# 230C_12V_PSU_TPS40200.net
KiCad netlist of a schematic drawn in Altium Designer
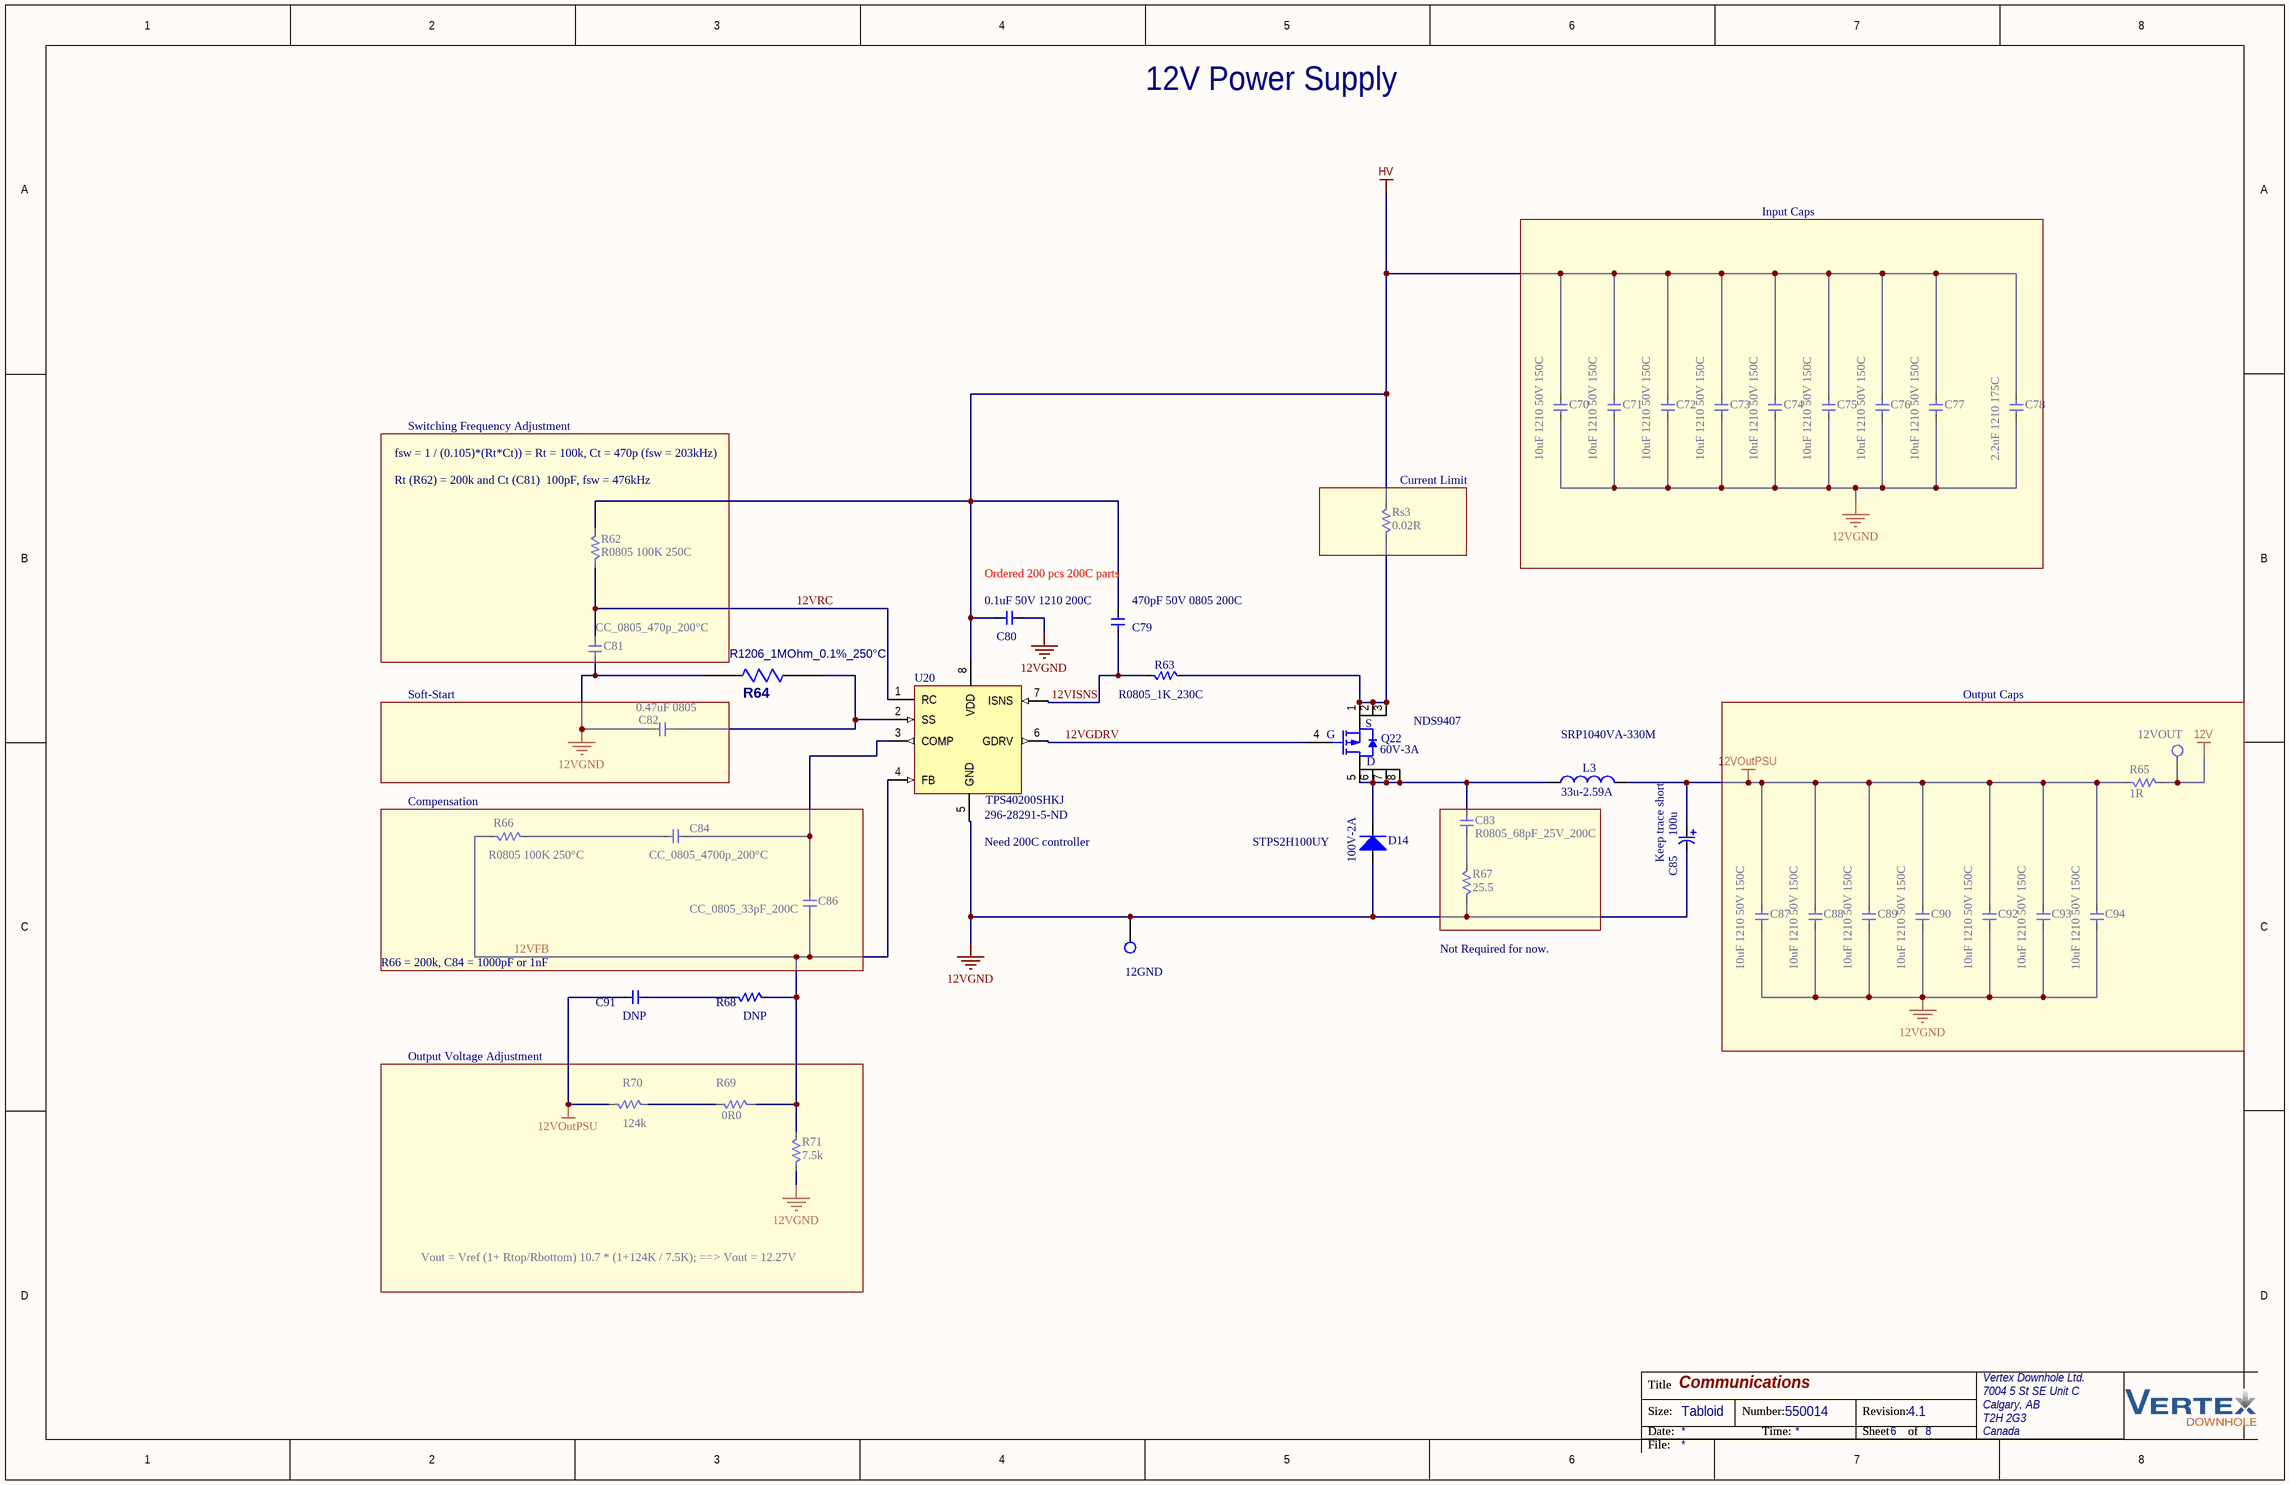
[diagram p0: 230C_12V_PSU_TPS40200.SchDoc]

(export (version "E")
  (design (tool "Eeschema 10.0.6"))
  (components
    (comp (ref "5")
      (value "12VOUT")
      (footprint "TP-S")
      (description "Test  Point")
      (libsource (lib "Miscellaneous") (part "TP"))
    )
    (comp (ref "6")
      (value "12GND")
      (footprint "TP-S")
      (description "Test  Point")
      (libsource (lib "Miscellaneous") (part "TP"))
    )
    (comp (ref "C70")
      (value "10uF 1210 50V 150C")
      (footprint "1210")
      (description "CAP CER 0.1UF 50V C0G/NP0 1210 200C")
      (fields (field (name "VOLTAGE") "50V") (field (name "TOLERANCE") "±10%"))
      (libsource (lib "230C_PSU_TPS40200") (part "CC-1210"))
    )
    (comp (ref "C71")
      (value "10uF 1210 50V 150C")
      (footprint "1210")
      (description "CAP CER 0.1UF 50V C0G/NP0 1210 200C")
      (fields (field (name "VOLTAGE") "50V") (field (name "TOLERANCE") "±5%"))
      (libsource (lib "230C_PSU_TPS40200") (part "CC-1210"))
    )
    (comp (ref "C72")
      (value "10uF 1210 50V 150C")
      (footprint "1210")
      (description "CAP CER 0.1UF 50V C0G/NP0 1210 200C")
      (fields (field (name "VOLTAGE") "50V") (field (name "TOLERANCE") "±5%"))
      (libsource (lib "230C_PSU_TPS40200") (part "CC-1210"))
    )
    (comp (ref "C73")
      (value "10uF 1210 50V 150C")
      (footprint "1210")
      (description "CAP CER 0.1UF 50V C0G/NP0 1210 200C")
      (fields (field (name "VOLTAGE") "50V") (field (name "TOLERANCE") "±5%"))
      (libsource (lib "230C_PSU_TPS40200") (part "CC-1210"))
    )
    (comp (ref "C74")
      (value "10uF 1210 50V 150C")
      (footprint "1210")
      (description "CAP CER 0.1UF 50V C0G/NP0 1210 200C")
      (fields (field (name "VOLTAGE") "50V") (field (name "TOLERANCE") "±5%"))
      (libsource (lib "230C_PSU_TPS40200") (part "CC-1210"))
    )
    (comp (ref "C75")
      (value "10uF 1210 50V 150C")
      (footprint "1210")
      (description "CAP CER 0.1UF 50V C0G/NP0 1210 200C")
      (fields (field (name "VOLTAGE") "50V") (field (name "TOLERANCE") "±5%"))
      (libsource (lib "230C_PSU_TPS40200") (part "CC-1210"))
    )
    (comp (ref "C76")
      (value "10uF 1210 50V 150C")
      (footprint "1210")
      (description "CAP CER 0.1UF 50V C0G/NP0 1210 200C")
      (fields (field (name "VOLTAGE") "50V") (field (name "TOLERANCE") "±5%"))
      (libsource (lib "230C_PSU_TPS40200") (part "CC-1210"))
    )
    (comp (ref "C77")
      (value "10uF 1210 50V 150C")
      (footprint "1210")
      (description "CAP CER 0.1UF 50V C0G/NP0 1210 200C")
      (fields (field (name "VOLTAGE") "50V") (field (name "TOLERANCE") "±5%"))
      (libsource (lib "230C_PSU_TPS40200") (part "CC-1210"))
    )
    (comp (ref "C78")
      (value "2.2uF 1210 175C")
      (footprint "1210")
      (description "CAP CER 0.1UF 50V C0G/NP0 1210 200C")
      (fields (field (name "VOLTAGE") "25V") (field (name "TOLERANCE") "±5%"))
      (libsource (lib "230C_PSU_TPS40200") (part "CC-1210"))
    )
    (comp (ref "C79")
      (value "470pF 50V 0805 200C")
      (footprint "1210")
      (description "CAP CER 470PF 50V C0G/NP0 0805 200C")
      (fields (field (name "VOLTAGE") "100V") (field (name "TOLERANCE") "±5%"))
      (libsource (lib "Schlib_CES2018") (part "CC-0805-100p-100V-10%-200C-NP0"))
    )
    (comp (ref "C80")
      (value "0.1uF 50V 1210 200C")
      (footprint "0805")
      (description "CAP CER 0.1UF 50V C0G/NP0 1210 200C")
      (fields (field (name "VOLTAGE") "25V") (field (name "TOLERANCE") "±5%"))
      (libsource (lib "230C_PSU_TPS40200") (part "CC-1210"))
    )
    (comp (ref "C81")
      (value "CC_0805_470p_200°C")
      (footprint "0805")
      (description "CAPACITOR CER 470PF 100V C0G/NP0 0805")
      (fields (field (name "VOLTAGE") "100V") (field (name "TOLERANCE") "±10%"))
      (libsource (lib "Integrated_Library_CES2018") (part "CC-0805-470p-100V-10%-150C-NP0"))
    )
    (comp (ref "C82")
      (value "0.47uF 0805")
      (footprint "0805")
      (description "CAPACITOR CER 0.047UF 25V C0G/NP0 0805")
      (fields (field (name "VOLTAGE") "25V") (field (name "TOLERANCE") "±5%"))
      (libsource (lib "Integrated_Library_CES2018") (part "CC-0805-47n-25V-5%-125C-NP0"))
    )
    (comp (ref "C83")
      (value "R0805_68pF_25V_200C")
      (footprint "0805")
      (description "CAPACITOR CER 2200PF 100V C0G/NP0 0805")
      (fields (field (name "VOLTAGE") "100V") (field (name "TOLERANCE") "±5%"))
      (libsource (lib "Schlib_CES2018") (part "CC-0805-2200p-100V-5%-200C-NP0"))
    )
    (comp (ref "C84")
      (value "CC_0805_4700p_200°C")
      (footprint "0805")
      (description "CAPACITOR CER 2200PF 100V C0G/NP0 0805")
      (fields (field (name "VOLTAGE") "100V") (field (name "TOLERANCE") "±5%"))
      (libsource (lib "Schlib_CES2018") (part "CC-0805-2200p-100V-5%-200C-NP0"))
    )
    (comp (ref "C85")
      (value "100u")
      (footprint "0805")
      (description "CAPACITOR TANT 100UF 16V 10% 2917")
      (fields (field (name "VOLTAGE") "16V") (field (name "TOLERANCE") "±10%"))
      (libsource (lib "Integrated_Library_CES2018") (part "CT-2917-100u-16V-10%-150C"))
    )
    (comp (ref "C86")
      (value "CC_0805_33pF_200C")
      (footprint "1210")
      (description "CAPACITOR CER 120PF 250V NP0 0805")
      (fields (field (name "VOLTAGE") "250V") (field (name "TOLERANCE") "±5%"))
      (libsource (lib "Schlib_CES2018") (part "CC-0805-120p-100V-5%-200C-NP0"))
    )
    (comp (ref "C87")
      (value "10uF 1210 50V 150C")
      (footprint "1210")
      (description "CAP CER 0.1UF 50V C0G/NP0 1210 200C")
      (fields (field (name "VOLTAGE") "50V") (field (name "TOLERANCE") "±10%"))
      (libsource (lib "230C_PSU_TPS40200") (part "CC-1210"))
    )
    (comp (ref "C88")
      (value "10uF 1210 50V 150C")
      (footprint "1210")
      (description "CAP CER 0.1UF 50V C0G/NP0 1210 200C")
      (fields (field (name "VOLTAGE") "50V") (field (name "TOLERANCE") "±5%"))
      (libsource (lib "230C_PSU_TPS40200") (part "CC-1210"))
    )
    (comp (ref "C89")
      (value "10uF 1210 50V 150C")
      (footprint "1210")
      (description "CAP CER 0.1UF 50V C0G/NP0 1210 200C")
      (fields (field (name "VOLTAGE") "50V") (field (name "TOLERANCE") "±5%"))
      (libsource (lib "230C_PSU_TPS40200") (part "CC-1210"))
    )
    (comp (ref "C90")
      (value "10uF 1210 50V 150C")
      (footprint "1210")
      (description "CAP CER 0.1UF 50V C0G/NP0 1210 200C")
      (fields (field (name "VOLTAGE") "50V") (field (name "TOLERANCE") "±5%"))
      (libsource (lib "230C_PSU_TPS40200") (part "CC-1210"))
    )
    (comp (ref "C91")
      (value "C1206H104J3GACTU")
      (footprint "0603")
      (description "CAPACITOR CER 2700PF 50V X8R 0805")
      (libsource (lib "Integrated_Library_Greg") (part "CC-0805-2700p-50V-10%-150C"))
    )
    (comp (ref "C92")
      (value "10uF 1210 50V 150C")
      (footprint "1210")
      (description "CAP CER 0.1UF 50V C0G/NP0 1210 200C")
      (fields (field (name "VOLTAGE") "50V") (field (name "TOLERANCE") "±5%"))
      (libsource (lib "230C_PSU_TPS40200") (part "CC-1210"))
    )
    (comp (ref "C93")
      (value "10uF 1210 50V 150C")
      (footprint "1210")
      (description "CAP CER 0.1UF 50V C0G/NP0 1210 200C")
      (fields (field (name "VOLTAGE") "50V") (field (name "TOLERANCE") "±5%"))
      (libsource (lib "230C_PSU_TPS40200") (part "CC-1210"))
    )
    (comp (ref "C94")
      (value "10uF 1210 50V 150C")
      (footprint "1210")
      (description "CAP CER 0.1UF 50V C0G/NP0 1210 200C")
      (fields (field (name "VOLTAGE") "50V") (field (name "TOLERANCE") "±5%"))
      (libsource (lib "230C_PSU_TPS40200") (part "CC-1210"))
    )
    (comp (ref "D14")
      (value "100V-2A")
      (footprint "SMB")
      (description "DIODE SCHOTTKY 100V 2A SMB")
      (fields (field (name "VOLTAGE") "100V") (field (name "MFG") "STMicroelectronics"))
      (libsource (lib "Integrated_Library_CES2018") (part "DS-SMB-100V-2A"))
    )
    (comp (ref "L3")
      (value "33u-2.59A")
      (footprint "IND_CB_DRA125")
      (description "INDUCTOR 47UH 2.59A 81 MOHM")
      (fields (field (name "MFG") "Eaton") (field (name "TOLERANCE") "±20%"))
      (libsource (lib "Integrated_Library_CES2018") (part "LL-12.5X12.5-47u-2.59A"))
    )
    (comp (ref "Q22")
      (value "60V-3A")
      (footprint "SOIC_S9407_ONS")
      (description "MOSFET P-CH 60V 3A 8-SOIC")
      (fields (field (name "VOLTAGE") "60V") (field (name "MFG") "ON Semiconductor"))
      (libsource (lib "Integrated_Library_CES2018") (part "QF-SOIC8-PCH-60V-3A"))
    )
    (comp (ref "R62")
      (value "R0805 100K 250C")
      (footprint "0805")
      (description "100 kOhms ±0.1% 0.2W, 1/5W Chip Resistor 0805 (2012 Metric)")
      (fields (field (name "TOLERANCE") "±0.1%") (field (name "MFG") "Vishay Dale Thin Film"))
      (libsource (lib "Schlib_CES2018") (part "RS-0805-9.1K-0.1%-1/4W-155C"))
    )
    (comp (ref "R63")
      (value "R0805_1K_230C")
      (footprint "0805")
      (description "RESISTOR SMD 1K OHM 0.1% 1/8W 0805")
      (fields (field (name "TOLERANCE") "±1%") (field (name "MFG") "Vishay / Sfernice"))
      (libsource (lib "Schlib_CES2018") (part "RS-0805-1K-0.1%-1/8W-155C"))
    )
    (comp (ref "R64")
      (value "R1206_1MOhm_0.1%_250°C")
      (footprint "1206")
      (description "1206")
      (fields (field (name "MPN") "PATT1206E1004BGT1") (field (name "MFR") "Vishay Dale Thin Film"))
      (libsource (lib "BJPPS") (part "RC_1206"))
    )
    (comp (ref "R65")
      (value "1R")
      (footprint "0805")
      (description "RESISTOR SMD 1 OHM 1% 1/4W 0805")
      (fields (field (name "TOLERANCE") "±1%") (field (name "MFG") "Stackpole Electronics Inc."))
      (libsource (lib "Integrated_Library_Greg") (part "RS-0805-1R-1%-0.25W-155C"))
    )
    (comp (ref "R66")
      (value "R0805 100K 250°C")
      (footprint "0805")
      (description "100 kOhms ±0.1% 0.2W, 1/5W Chip Resistor 0805 (2012 Metric)")
      (fields (field (name "TOLERANCE") "±0.1%") (field (name "MFG") "Vishay Dale Thin Film"))
      (libsource (lib "Schlib_CES2018") (part "RS-0805-9.1K-0.1%-1/4W-155C"))
    )
    (comp (ref "R67")
      (value "25.5")
      (footprint "0805")
      (description "RESISTOR SMD 10.2K OHM 1% 1/4W 0805")
      (fields (field (name "TOLERANCE") "±1%") (field (name "MFG") "Panasonic Electronic Components"))
      (libsource (lib "Schlib_CES2018") (part "RS-0805-10.2K-0.1%-0.25W-155C"))
    )
    (comp (ref "R68")
      (value "ERJ-PB6B6812V")
      (footprint "0805")
      (description "RESISTOR SMD 475 OHM 0.1% 1/10W 0805")
      (libsource (lib "Schlib_CES2018") (part "RS-0805-475R-0.1%-0.25W-155C"))
    )
    (comp (ref "R69")
      (value "0R0")
      (footprint "0805")
      (fields
        (field (name "TOLERANCE") "±0.1%")
        (field (name "MFG") "Vishay Dale Thin Film")
        (field (name "POWER") "0.250W")
      )
      (libsource (lib "Schlib_CES2018") (part "RS-0805-1.5K-0.1%-1/4W-155C"))
    )
    (comp (ref "R70")
      (value "124k")
      (footprint "0805")
      (description "100 kOhms ±0.1% 0.2W, 1/5W Chip Resistor 0805 (2012 Metric)")
      (fields (field (name "TOLERANCE") "±0.1%") (field (name "MFG") "Vishay Dale Thin Film"))
      (libsource (lib "Schlib_CES2018") (part "RS-0805-9.1K-0.1%-1/4W-155C"))
    )
    (comp (ref "R71")
      (value "7.5k")
      (footprint "0805")
      (description "RESISTOR SMD 49.9 OHM 0.1% 1/25W 0805")
      (fields (field (name "TOLERANCE") "±0.1%") (field (name "MFG") "KOA Speer Electronics, Inc."))
      (libsource (lib "Schlib_CES2018") (part "RS-0805-49.9R-0.25%-0.25W-155C"))
    )
    (comp (ref "Rs3")
      (value "0.02R")
      (footprint "1206")
      (description "RESISTOR SMD 0.02 OHM 1% 1W 1206")
      (fields (field (name "TOLERANCE") "±1%") (field (name "MFG") "Panasonic Electronic Components"))
      (libsource (lib "Integrated_Library_CES2018") (part "RS-1206-0.02R-1%-1W-155C"))
    )
    (comp (ref "U20")
      (value "TPS40200SHKJ")
      (footprint "SOIC_S9407_ONS")
      (description "IC REG CTRLR BUCK 8CFP")
      (fields
        (field (name "MFG") "Texas Instruments")
        (field (name "SUPPLIER PART NUMBER 1") "296-28291-5-ND")
      )
      (libsource (lib "Integrated_Library_CES2018") (part "UP-SREG-CFP8-Buck-ADJ-TPS40200"))
    )
  )
  (nets
    (net (code "1") (name "/12VFB") (class "Default")
      (node (ref "C86") (pin "1") (pinfunction "1_1") (pintype "passive"))
      (node (ref "R66") (pin "1") (pinfunction "1_1") (pintype "passive"))
      (node (ref "R68") (pin "2") (pinfunction "2_2") (pintype "passive"))
      (node (ref "R69") (pin "1") (pinfunction "1_1") (pintype "passive"))
      (node (ref "R71") (pin "2") (pinfunction "2_2") (pintype "passive"))
      (node (ref "U20") (pin "4") (pinfunction "FB_4") (pintype "input"))
    )
    (net (code "2") (name "/12VGDRV") (class "Default")
      (node (ref "Q22") (pin "4") (pinfunction "G_4") (pintype "passive"))
      (node (ref "U20") (pin "6") (pinfunction "GDRV_6") (pintype "output"))
    )
    (net (code "3") (name "/12VISNS") (class "Default")
      (node (ref "C79") (pin "2") (pinfunction "2_2") (pintype "passive"))
      (node (ref "R63") (pin "1") (pinfunction "1_1") (pintype "passive"))
      (node (ref "U20") (pin "7") (pinfunction "ISNS_7") (pintype "input"))
    )
    (net (code "4") (name "/12VRC") (class "Default")
      (node (ref "C81") (pin "2") (pinfunction "2_2") (pintype "passive"))
      (node (ref "R62") (pin "1") (pinfunction "1_1") (pintype "passive"))
      (node (ref "U20") (pin "1") (pinfunction "RC_1") (pintype "passive"))
    )
    (net (code "5") (name "12V") (class "Default")
      (node (ref "5") (pin "1") (pinfunction "1_1") (pintype "passive"))
      (node (ref "R65") (pin "2") (pinfunction "2_2") (pintype "passive"))
    )
    (net (code "6") (name "12VGND") (class "Default")
      (node (ref "6") (pin "1") (pinfunction "1_1") (pintype "passive"))
      (node (ref "C70") (pin "1") (pinfunction "1_1") (pintype "passive"))
      (node (ref "C71") (pin "1") (pinfunction "1_1") (pintype "passive"))
      (node (ref "C72") (pin "1") (pinfunction "1_1") (pintype "passive"))
      (node (ref "C73") (pin "1") (pinfunction "1_1") (pintype "passive"))
      (node (ref "C74") (pin "1") (pinfunction "1_1") (pintype "passive"))
      (node (ref "C75") (pin "1") (pinfunction "1_1") (pintype "passive"))
      (node (ref "C76") (pin "1") (pinfunction "1_1") (pintype "passive"))
      (node (ref "C77") (pin "1") (pinfunction "1_1") (pintype "passive"))
      (node (ref "C78") (pin "1") (pinfunction "1_1") (pintype "passive"))
      (node (ref "C80") (pin "2") (pinfunction "2_2") (pintype "passive"))
      (node (ref "C81") (pin "1") (pinfunction "1_1") (pintype "passive"))
      (node (ref "C82") (pin "1") (pinfunction "1_1") (pintype "passive"))
      (node (ref "C85") (pin "2") (pinfunction "2_2") (pintype "passive"))
      (node (ref "C87") (pin "1") (pinfunction "1_1") (pintype "passive"))
      (node (ref "C88") (pin "1") (pinfunction "1_1") (pintype "passive"))
      (node (ref "C89") (pin "1") (pinfunction "1_1") (pintype "passive"))
      (node (ref "C90") (pin "1") (pinfunction "1_1") (pintype "passive"))
      (node (ref "C92") (pin "1") (pinfunction "1_1") (pintype "passive"))
      (node (ref "C93") (pin "1") (pinfunction "1_1") (pintype "passive"))
      (node (ref "C94") (pin "1") (pinfunction "1_1") (pintype "passive"))
      (node (ref "D14") (pin "A") (pinfunction "A_A") (pintype "passive"))
      (node (ref "R64") (pin "1") (pinfunction "A_1") (pintype "passive"))
      (node (ref "R67") (pin "1") (pinfunction "1_1") (pintype "passive"))
      (node (ref "R71") (pin "1") (pinfunction "1_1") (pintype "passive"))
      (node (ref "U20") (pin "5") (pinfunction "GND_5") (pintype "passive"))
    )
    (net (code "7") (name "12VOutPSU") (class "Default")
      (node (ref "C85") (pin "1") (pinfunction "1_1") (pintype "passive"))
      (node (ref "C87") (pin "2") (pinfunction "2_2") (pintype "passive"))
      (node (ref "C88") (pin "2") (pinfunction "2_2") (pintype "passive"))
      (node (ref "C89") (pin "2") (pinfunction "2_2") (pintype "passive"))
      (node (ref "C90") (pin "2") (pinfunction "2_2") (pintype "passive"))
      (node (ref "C91") (pin "1") (pinfunction "1_1") (pintype "passive"))
      (node (ref "C92") (pin "2") (pinfunction "2_2") (pintype "passive"))
      (node (ref "C93") (pin "2") (pinfunction "2_2") (pintype "passive"))
      (node (ref "C94") (pin "2") (pinfunction "2_2") (pintype "passive"))
      (node (ref "L3") (pin "2") (pinfunction "2_2") (pintype "passive"))
      (node (ref "R65") (pin "1") (pinfunction "1_1") (pintype "passive"))
      (node (ref "R70") (pin "1") (pinfunction "1_1") (pintype "passive"))
    )
    (net (code "8") (name "HV") (class "Default")
      (node (ref "C70") (pin "2") (pinfunction "2_2") (pintype "passive"))
      (node (ref "C71") (pin "2") (pinfunction "2_2") (pintype "passive"))
      (node (ref "C72") (pin "2") (pinfunction "2_2") (pintype "passive"))
      (node (ref "C73") (pin "2") (pinfunction "2_2") (pintype "passive"))
      (node (ref "C74") (pin "2") (pinfunction "2_2") (pintype "passive"))
      (node (ref "C75") (pin "2") (pinfunction "2_2") (pintype "passive"))
      (node (ref "C76") (pin "2") (pinfunction "2_2") (pintype "passive"))
      (node (ref "C77") (pin "2") (pinfunction "2_2") (pintype "passive"))
      (node (ref "C78") (pin "2") (pinfunction "2_2") (pintype "passive"))
      (node (ref "C79") (pin "1") (pinfunction "1_1") (pintype "passive"))
      (node (ref "C80") (pin "1") (pinfunction "1_1") (pintype "passive"))
      (node (ref "R62") (pin "2") (pinfunction "2_2") (pintype "passive"))
      (node (ref "Rs3") (pin "2") (pinfunction "2_2") (pintype "passive"))
      (node (ref "U20") (pin "8") (pinfunction "VDD_8") (pintype "power_in"))
    )
    (net (code "9") (name "Net-(C83-Pad1)") (class "Default")
      (node (ref "C83") (pin "1") (pinfunction "1_1") (pintype "passive"))
      (node (ref "R67") (pin "2") (pinfunction "2_2") (pintype "passive"))
    )
    (net (code "10") (name "Net-(C83-Pad2)") (class "Default")
      (node (ref "C83") (pin "2") (pinfunction "2_2") (pintype "passive"))
      (node (ref "D14") (pin "K") (pinfunction "K_K") (pintype "passive"))
      (node (ref "L3") (pin "1") (pinfunction "1_1") (pintype "passive"))
      (node (ref "Q22") (pin "5") (pinfunction "D_5") (pintype "passive"))
      (node (ref "Q22") (pin "6") (pinfunction "D_6") (pintype "passive"))
      (node (ref "Q22") (pin "7") (pinfunction "D_7") (pintype "passive"))
      (node (ref "Q22") (pin "8") (pinfunction "D_8") (pintype "passive"))
    )
    (net (code "11") (name "Net-(C84-Pad1)") (class "Default")
      (node (ref "C84") (pin "1") (pinfunction "1_1") (pintype "passive"))
      (node (ref "R66") (pin "2") (pinfunction "2_2") (pintype "passive"))
    )
    (net (code "12") (name "Net-(C91-Pad2)") (class "Default")
      (node (ref "C91") (pin "2") (pinfunction "2_2") (pintype "passive"))
      (node (ref "R68") (pin "1") (pinfunction "1_1") (pintype "passive"))
    )
    (net (code "13") (name "Net-(Q22-S-Pad1)") (class "Default")
      (node (ref "Q22") (pin "1") (pinfunction "S_1") (pintype "passive"))
      (node (ref "Q22") (pin "2") (pinfunction "S_2") (pintype "passive"))
      (node (ref "Q22") (pin "3") (pinfunction "S_3") (pintype "passive"))
      (node (ref "R63") (pin "2") (pinfunction "2_2") (pintype "passive"))
      (node (ref "Rs3") (pin "1") (pinfunction "1_1") (pintype "passive"))
    )
    (net (code "14") (name "Net-(R64-B)") (class "Default")
      (node (ref "C82") (pin "2") (pinfunction "2_2") (pintype "passive"))
      (node (ref "R64") (pin "2") (pinfunction "B_2") (pintype "passive"))
      (node (ref "U20") (pin "2") (pinfunction "SS_2") (pintype "input"))
    )
    (net (code "15") (name "Net-(R69-Pad2)") (class "Default")
      (node (ref "R69") (pin "2") (pinfunction "2_2") (pintype "passive"))
      (node (ref "R70") (pin "2") (pinfunction "2_2") (pintype "passive"))
    )
    (net (code "16") (name "Net-(U20-COMP)") (class "Default")
      (node (ref "C84") (pin "2") (pinfunction "2_2") (pintype "passive"))
      (node (ref "C86") (pin "2") (pinfunction "2_2") (pintype "passive"))
      (node (ref "U20") (pin "3") (pinfunction "COMP_3") (pintype "output"))
    )
  )
)
